# encoder_breakout.net
KiCad netlist of a schematic drawn in Altium Designer
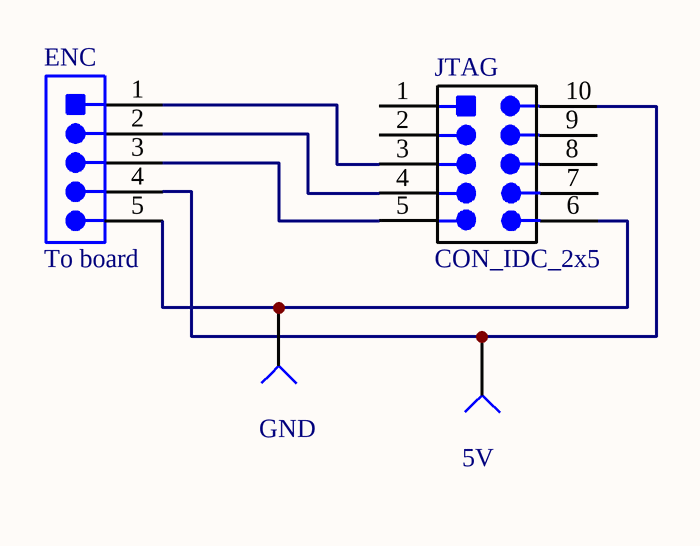
[diagram p0: encoder_breakout.SchDoc]

(export (version "E")
  (design (tool "Eeschema 10.0.6"))
  (components
    (comp (ref "ENC")
      (value "To board")
      (footprint "JST-S5B-SM4-TB")
      (libsource (lib "UWRT_Schematic_Library_2019") (part "CON_5M"))
    )
    (comp (ref "JTAG")
      (value "CON_IDC_2x5")
      (footprint "IDC HEADER")
      (libsource (lib "UWRT_Schematic_Library_2019") (part "CON_IDC_2x5"))
    )
    (comp (ref "TP1")
      (value "GND")
      (footprint "TESTPOINT")
      (description "TESTPOINT_SMD")
      (libsource (lib "UWRT_Schematic_Library_2019") (part "*"))
    )
    (comp (ref "TP2")
      (value "5V")
      (footprint "TESTPOINT")
      (description "TESTPOINT_SMD")
      (libsource (lib "UWRT_Schematic_Library_2019") (part "*"))
    )
  )
  (nets
    (net (code "1") (name "Net-(ENC-Pad1)") (class "Default")
      (node (ref "ENC") (pin "1") (pinfunction "1_1") (pintype "passive"))
      (node (ref "JTAG") (pin "3") (pinfunction "3_3") (pintype "passive"))
    )
    (net (code "2") (name "Net-(ENC-Pad2)") (class "Default")
      (node (ref "ENC") (pin "2") (pinfunction "2_2") (pintype "passive"))
      (node (ref "JTAG") (pin "4") (pinfunction "4_4") (pintype "passive"))
    )
    (net (code "3") (name "Net-(ENC-Pad3)") (class "Default")
      (node (ref "ENC") (pin "3") (pinfunction "3_3") (pintype "passive"))
      (node (ref "JTAG") (pin "5") (pinfunction "5_5") (pintype "passive"))
    )
    (net (code "4") (name "Net-(TP1-=value)") (class "Default")
      (node (ref "ENC") (pin "5") (pinfunction "5_5") (pintype "passive"))
      (node (ref "JTAG") (pin "6") (pinfunction "6_6") (pintype "passive"))
      (node (ref "TP1") (pin "1") (pinfunction "=value_1") (pintype "passive"))
    )
    (net (code "5") (name "Net-(TP2-=value)") (class "Default")
      (node (ref "ENC") (pin "4") (pinfunction "4_4") (pintype "passive"))
      (node (ref "JTAG") (pin "10") (pinfunction "10_10") (pintype "passive"))
      (node (ref "TP2") (pin "1") (pinfunction "=value_1") (pintype "passive"))
    )
    (net (code "6") (name "unconnected-(JTAG-Pad1)") (class "Default")
      (node (ref "JTAG") (pin "1") (pinfunction "1_1") (pintype "passive"))
    )
    (net (code "7") (name "unconnected-(JTAG-Pad2)") (class "Default")
      (node (ref "JTAG") (pin "2") (pinfunction "2_2") (pintype "passive"))
    )
    (net (code "8") (name "unconnected-(JTAG-Pad7)") (class "Default")
      (node (ref "JTAG") (pin "7") (pinfunction "7_7") (pintype "passive"))
    )
    (net (code "9") (name "unconnected-(JTAG-Pad8)") (class "Default")
      (node (ref "JTAG") (pin "8") (pinfunction "8_8") (pintype "passive"))
    )
    (net (code "10") (name "unconnected-(JTAG-Pad9)") (class "Default")
      (node (ref "JTAG") (pin "9") (pinfunction "9_9") (pintype "passive"))
    )
  )
)
